# NG2094_RIGHT_OV9282.net
KiCad netlist of a schematic drawn in Altium Designer
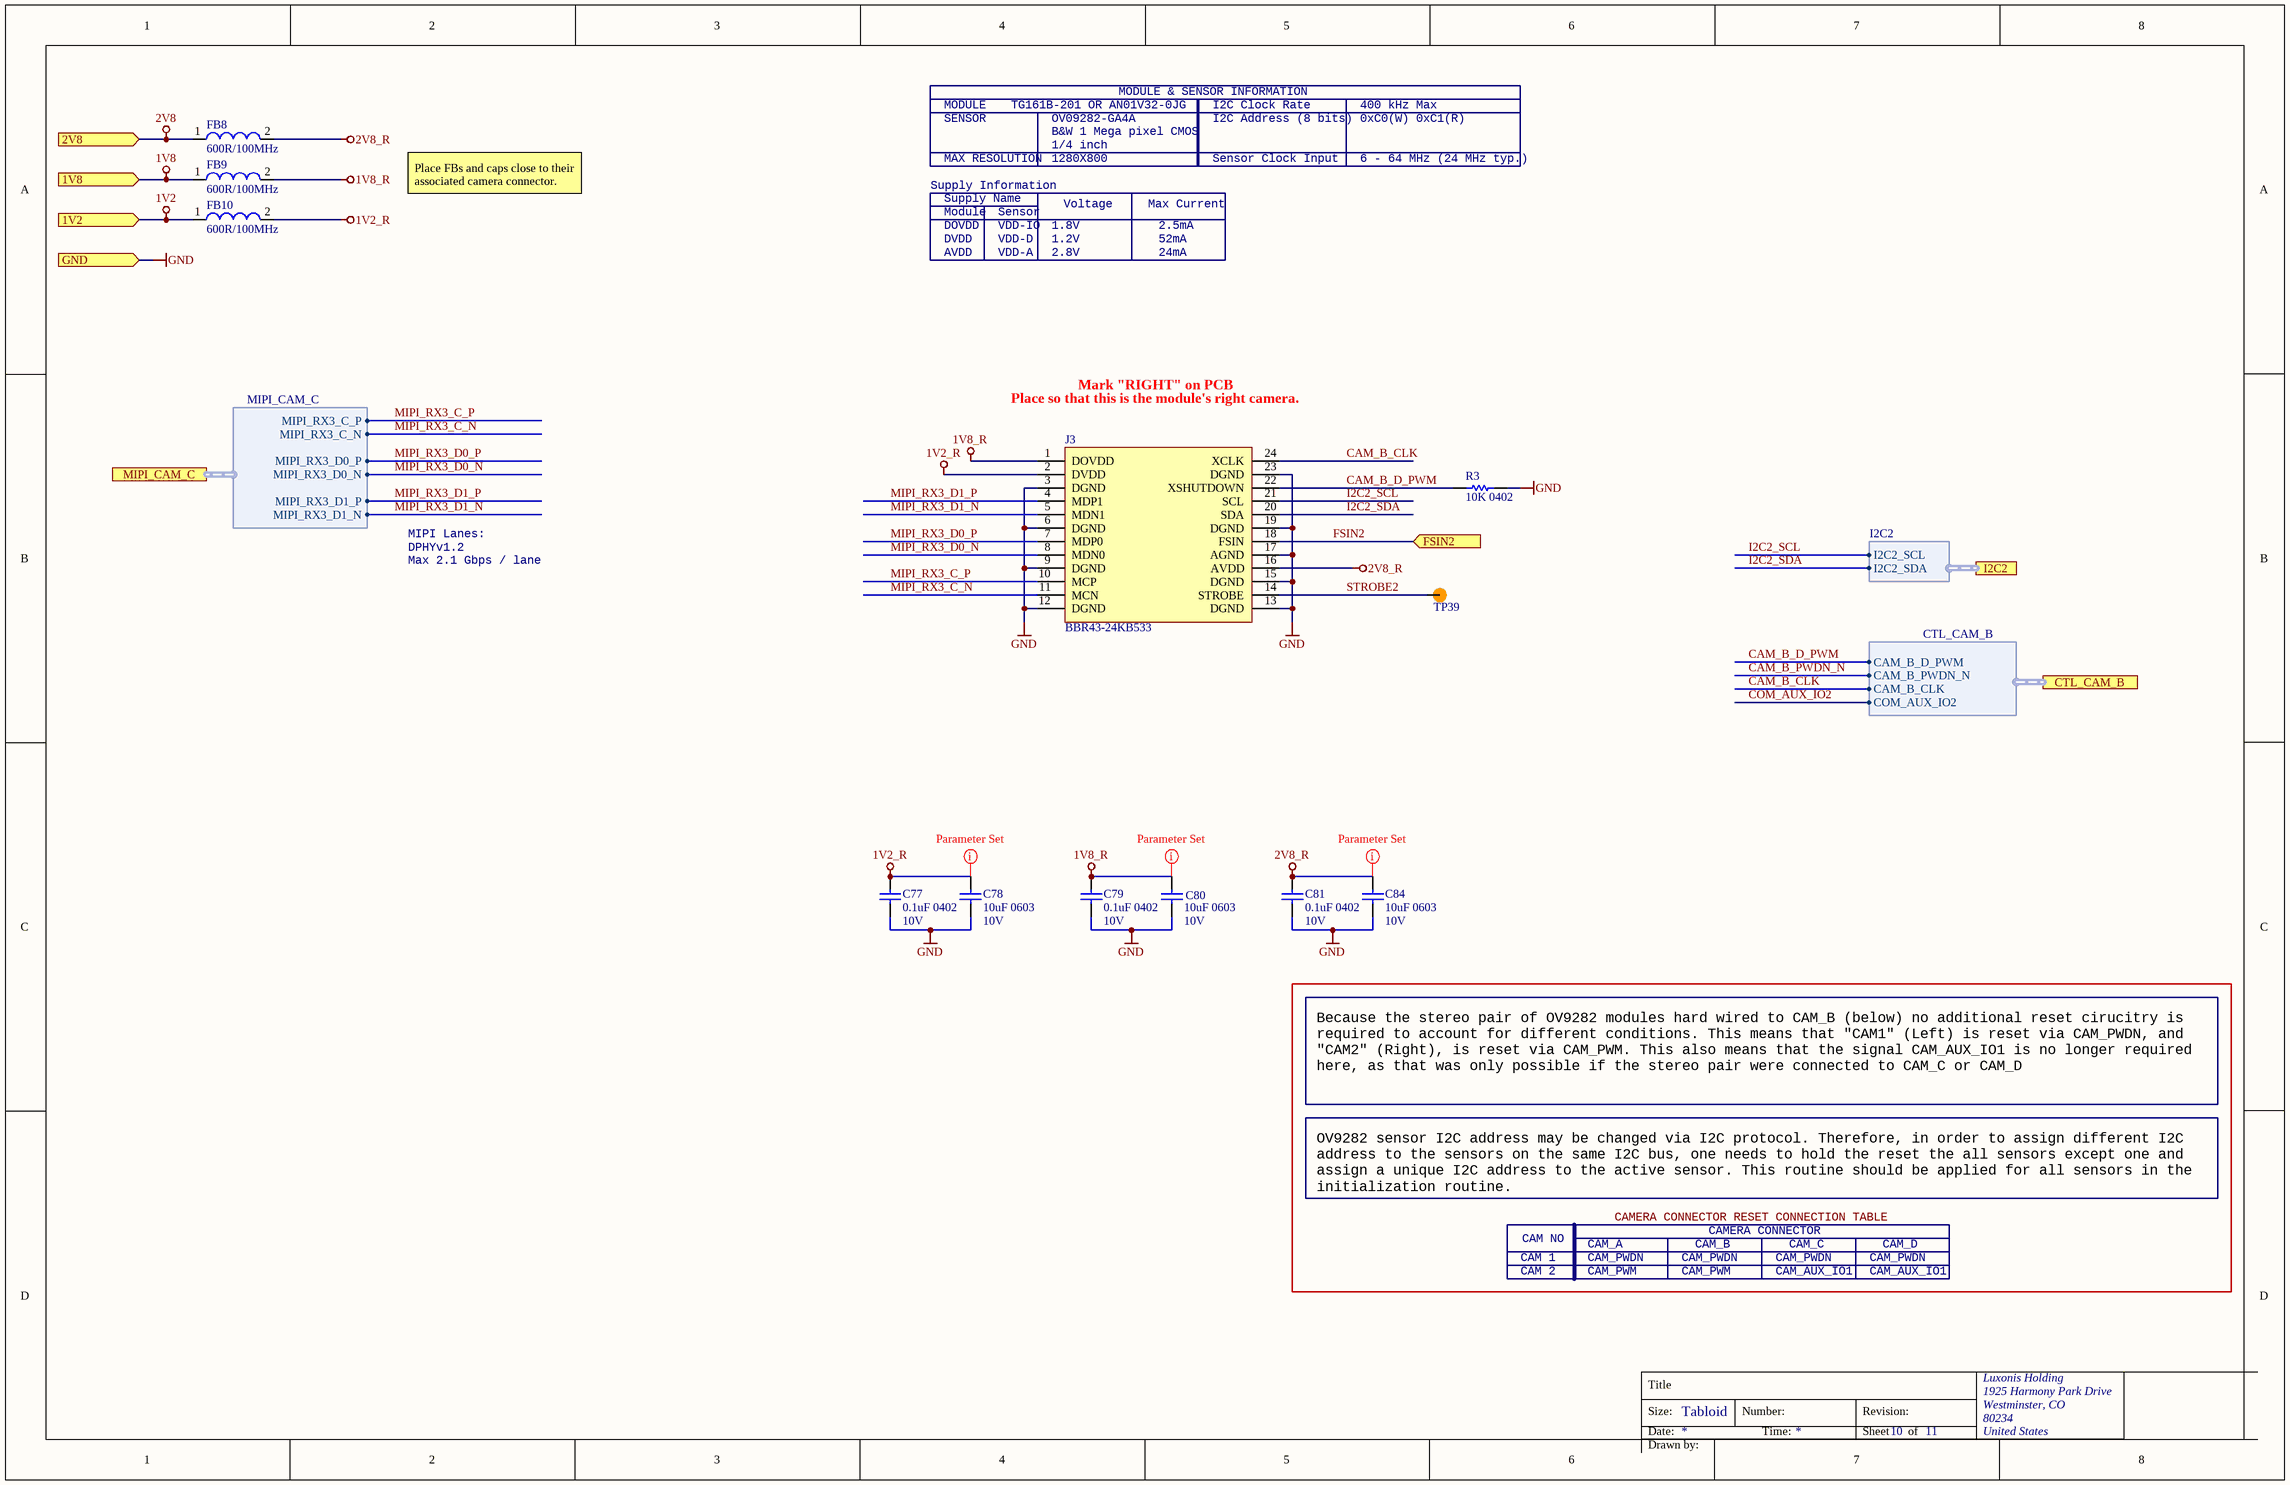
[diagram p0: NG2094_RIGHT_OV9282.SchDoc]

(export (version "E")
  (design (tool "Eeschema 10.0.6"))
  (components
    (comp (ref "C77")
      (value "0.1uF 0402")
      (footprint "CAP_Altium_Vault_Generic:CAPC0402(1005)70_L")
      (description "CAP CER 0.1UF 10V X7R 0402 5%")
      (fields (field (name "TOLERANCE") "5%") (field (name "VOLTAGE RATING") "10V"))
      (libsource (lib "LuxonisMaster") (part "GRM155R71A104JA01D"))
    )
    (comp (ref "C78")
      (value "10uF 0603")
      (footprint "CAP_Altium_Vault_Generic:CAPC0603(1608)100_L")
      (description "CAP CER 10UF 10V X5R 0603 20%")
      (fields (field (name "TOLERANCE") "20%") (field (name "VOLTAGE RATING") "10V"))
      (libsource (lib "LuxonisMaster") (part "GRM188R61A106ME69D"))
    )
    (comp (ref "C79")
      (value "0.1uF 0402")
      (footprint "CAP_Altium_Vault_Generic:CAPC0402(1005)70_L")
      (description "CAP CER 0.1UF 10V X7R 0402 5%")
      (fields (field (name "TOLERANCE") "5%") (field (name "VOLTAGE RATING") "10V"))
      (libsource (lib "LuxonisMaster") (part "GRM155R71A104JA01D"))
    )
    (comp (ref "C80")
      (value "10uF 0603")
      (footprint "CAP_Altium_Vault_Generic:CAPC0603(1608)100_L")
      (description "CAP CER 10UF 10V X5R 0603 20%")
      (fields (field (name "TOLERANCE") "20%") (field (name "VOLTAGE RATING") "10V"))
      (libsource (lib "LuxonisMaster") (part "GRM188R61A106ME69D"))
    )
    (comp (ref "C81")
      (value "0.1uF 0402")
      (footprint "CAP_Altium_Vault_Generic:CAPC0402(1005)70_L")
      (description "CAP CER 0.1UF 10V X7R 0402 5%")
      (fields (field (name "TOLERANCE") "5%") (field (name "VOLTAGE RATING") "10V"))
      (libsource (lib "LuxonisMaster") (part "GRM155R71A104JA01D"))
    )
    (comp (ref "C84")
      (value "10uF 0603")
      (footprint "CAP_Altium_Vault_Generic:CAPC0603(1608)100_L")
      (description "CAP CER 10UF 10V X5R 0603 20%")
      (fields (field (name "TOLERANCE") "20%") (field (name "VOLTAGE RATING") "10V"))
      (libsource (lib "LuxonisMaster") (part "GRM188R61A106ME69D"))
    )
    (comp (ref "FB8")
      (value "600R/100MHz")
      (footprint "LuxonisMaster:2508056017Y2")
      (description "FERRITE BEAD, 0.1OHM, 2A, 0805, 600R/100MHz")
      (fields (field (name "TOLERANCE") "25%"))
      (libsource (lib "LuxonisMaster") (part "2508056017Y2"))
    )
    (comp (ref "FB9")
      (value "600R/100MHz")
      (footprint "LuxonisMaster:2508056017Y2")
      (description "FERRITE BEAD, 0.1OHM, 2A, 0805, 600R/100MHz")
      (fields (field (name "TOLERANCE") "25%"))
      (libsource (lib "LuxonisMaster") (part "2508056017Y2"))
    )
    (comp (ref "FB10")
      (value "600R/100MHz")
      (footprint "LuxonisMaster:2508056017Y2")
      (description "FERRITE BEAD, 0.1OHM, 2A, 0805, 600R/100MHz")
      (fields (field (name "TOLERANCE") "25%"))
      (libsource (lib "LuxonisMaster") (part "2508056017Y2"))
    )
    (comp (ref "J3")
      (value "BBR43-24KB533")
      (footprint "TG161B-201_W")
      (description "CONN 24 way, 2 row board to board connector SMD")
      (libsource (lib "LuxonisMaster") (part "TG161B-201_Connector"))
    )
    (comp (ref "R3")
      (value "10K 0402")
      (footprint "RES_Altium_Vault_Generic:RESC0402(1005)_L")
      (fields (field (name "TOLERANCE") "1%"))
      (libsource (lib "LuxonisMaster") (part "RC0402FR-1310KL"))
    )
    (comp (ref "TP39")
      (value "TP100_200_NS")
      (footprint "LuxonisMaster:TP100_200_NS")
      (libsource (lib "LuxonisMaster") (part "TEST_POINT"))
    )
  )
  (nets
    (net (code "4") (name "/CAM_B_CLK") (class "Default")
      (node (ref "J3") (pin "24") (pinfunction "XCLK_24") (pintype "passive"))
    )
    (net (code "5") (name "/CAM_B_D_PWM") (class "Default")
      (node (ref "J3") (pin "22") (pinfunction "XSHUTDOWN_22") (pintype "passive"))
      (node (ref "R3") (pin "1") (pinfunction "1_1") (pintype "passive"))
    )
    (net (code "8") (name "/FSIN2") (class "Default")
      (node (ref "J3") (pin "18") (pinfunction "FSIN_18") (pintype "passive"))
    )
    (net (code "9") (name "/I2C2_SCL") (class "Default")
      (node (ref "J3") (pin "21") (pinfunction "SCL_21") (pintype "passive"))
    )
    (net (code "10") (name "/I2C2_SDA") (class "Default")
      (node (ref "J3") (pin "20") (pinfunction "SDA_20") (pintype "passive"))
    )
    (net (code "11") (name "/MIPI_RX3_C_N") (class "Default")
      (node (ref "J3") (pin "11") (pinfunction "MCN_11") (pintype "passive"))
    )
    (net (code "12") (name "/MIPI_RX3_C_P") (class "Default")
      (node (ref "J3") (pin "10") (pinfunction "MCP_10") (pintype "passive"))
    )
    (net (code "13") (name "/MIPI_RX3_D0_N") (class "Default")
      (node (ref "J3") (pin "8") (pinfunction "MDN0_8") (pintype "passive"))
    )
    (net (code "14") (name "/MIPI_RX3_D0_P") (class "Default")
      (node (ref "J3") (pin "7") (pinfunction "MDP0_7") (pintype "passive"))
    )
    (net (code "15") (name "/MIPI_RX3_D1_N") (class "Default")
      (node (ref "J3") (pin "5") (pinfunction "MDN1_5") (pintype "passive"))
    )
    (net (code "16") (name "/MIPI_RX3_D1_P") (class "Default")
      (node (ref "J3") (pin "4") (pinfunction "MDP1_4") (pintype "passive"))
    )
    (net (code "17") (name "/STROBE2") (class "Default")
      (node (ref "J3") (pin "14") (pinfunction "STROBE_14") (pintype "passive"))
      (node (ref "TP39") (pin "1") (pintype "passive"))
    )
    (net (code "21") (name "1V2") (class "Default")
      (node (ref "FB10") (pin "1") (pinfunction "1_1") (pintype "passive"))
    )
    (net (code "22") (name "1V2_R") (class "Default")
      (node (ref "C77") (pin "2") (pinfunction "2_2") (pintype "passive"))
      (node (ref "C78") (pin "2") (pinfunction "2_2") (pintype "passive"))
      (node (ref "FB10") (pin "2") (pinfunction "2_2") (pintype "passive"))
      (node (ref "J3") (pin "2") (pinfunction "DVDD_2") (pintype "passive"))
    )
    (net (code "23") (name "1V8") (class "Default")
      (node (ref "FB9") (pin "1") (pinfunction "1_1") (pintype "passive"))
    )
    (net (code "24") (name "1V8_R") (class "Default")
      (node (ref "C79") (pin "2") (pinfunction "2_2") (pintype "passive"))
      (node (ref "C80") (pin "2") (pinfunction "2_2") (pintype "passive"))
      (node (ref "FB9") (pin "2") (pinfunction "2_2") (pintype "passive"))
      (node (ref "J3") (pin "1") (pinfunction "DOVDD_1") (pintype "passive"))
    )
    (net (code "25") (name "2V8") (class "Default")
      (node (ref "FB8") (pin "1") (pinfunction "1_1") (pintype "passive"))
    )
    (net (code "26") (name "2V8_R") (class "Default")
      (node (ref "C81") (pin "2") (pinfunction "2_2") (pintype "passive"))
      (node (ref "C84") (pin "2") (pinfunction "2_2") (pintype "passive"))
      (node (ref "FB8") (pin "2") (pinfunction "2_2") (pintype "passive"))
      (node (ref "J3") (pin "16") (pinfunction "AVDD_16") (pintype "passive"))
    )
    (net (code "27") (name "GND") (class "Default")
      (node (ref "C77") (pin "1") (pinfunction "1_1") (pintype "passive"))
      (node (ref "C78") (pin "1") (pinfunction "1_1") (pintype "passive"))
      (node (ref "C79") (pin "1") (pinfunction "1_1") (pintype "passive"))
      (node (ref "C80") (pin "1") (pinfunction "1_1") (pintype "passive"))
      (node (ref "C81") (pin "1") (pinfunction "1_1") (pintype "passive"))
      (node (ref "C84") (pin "1") (pinfunction "1_1") (pintype "passive"))
      (node (ref "J3") (pin "12") (pinfunction "DGND_12") (pintype "passive"))
      (node (ref "J3") (pin "13") (pinfunction "DGND_13") (pintype "passive"))
      (node (ref "J3") (pin "15") (pinfunction "DGND_15") (pintype "passive"))
      (node (ref "J3") (pin "17") (pinfunction "AGND_17") (pintype "passive"))
      (node (ref "J3") (pin "19") (pinfunction "DGND_19") (pintype "passive"))
      (node (ref "J3") (pin "23") (pinfunction "DGND_23") (pintype "passive"))
      (node (ref "J3") (pin "3") (pinfunction "DGND_3") (pintype "passive"))
      (node (ref "J3") (pin "6") (pinfunction "DGND_6") (pintype "passive"))
      (node (ref "J3") (pin "9") (pinfunction "DGND_9") (pintype "passive"))
      (node (ref "R3") (pin "2") (pinfunction "2_2") (pintype "passive"))
    )
  )
)
